# ConectoresEntrada.net
KiCad netlist of a schematic drawn in Altium Designer
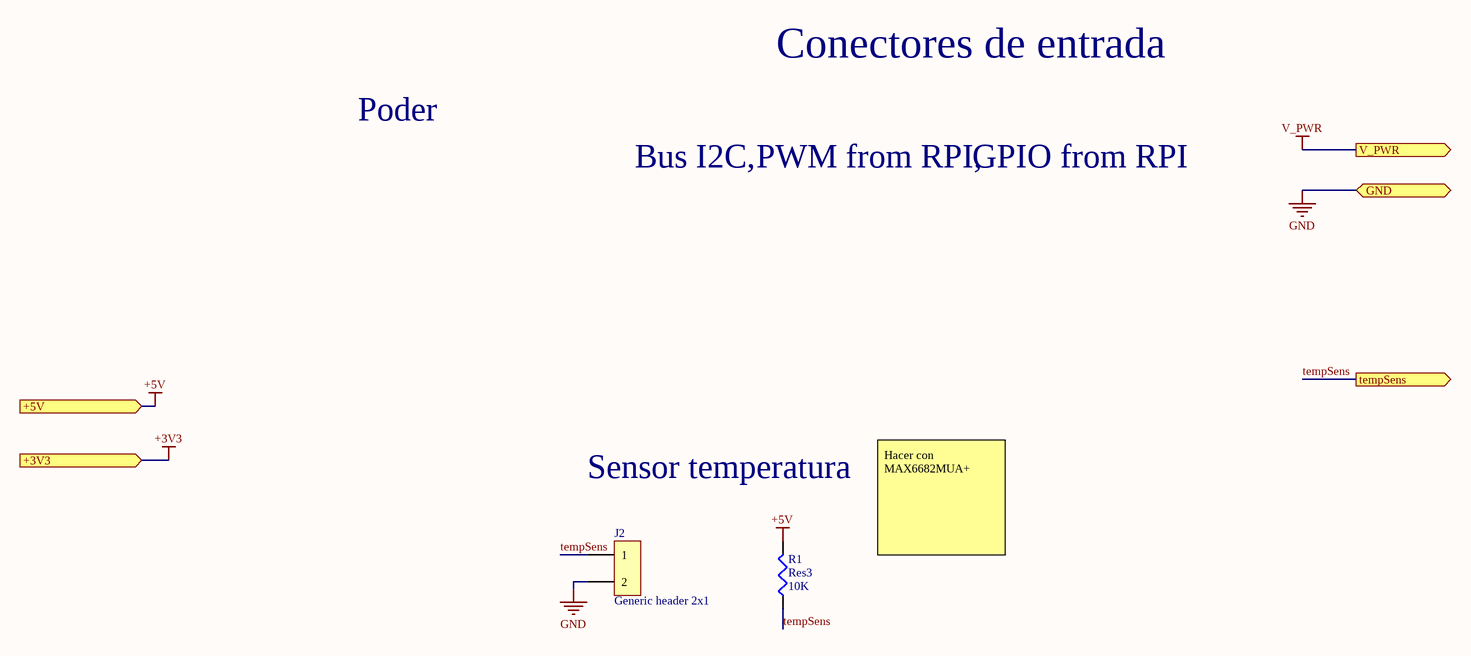
[diagram p0: ConectoresEntrada.SchDoc]

(export (version "E")
  (design (tool "Eeschema 10.0.6"))
  (components
    (comp (ref "J2")
      (value "Generic header 2x1")
      (footprint "CONN-TH_A2547WV-2P")
      (description "Generic Header 2pos, 1 row, 2.54 pitch")
      (fields
        (field (name "MANUFACTURER") "CJT(Changjiang Connectors)")
        (field (name "MANUFACTURER PART NUMBER") "A2547WV-2P")
      )
      (libsource (lib "IoWLabsConnectors") (part "Header - 2x1"))
    )
    (comp (ref "R1")
      (value "Res3")
      (footprint "J1-0603")
      (description "Resistor")
      (fields
        (field (name "ALTIUM_VALUE") "10K")
        (field (name "MANUFACTURER") "PANASONIC")
        (field (name "MANUFACTURER PART NUMBER") "ERJPA3F1002V")
        (field (name "PUBLISHER") "Altium Limited")
      )
      (libsource (lib "Miscellaneous Devices") (part "Res3"))
    )
  )
  (nets
    (net (code "2") (name "+5V") (class "Default")
      (node (ref "R1") (pin "2") (pinfunction "2_2") (pintype "passive"))
    )
    (net (code "3") (name "/tempSens") (class "Default")
      (node (ref "J2") (pin "1") (pinfunction "1_1") (pintype "passive"))
      (node (ref "R1") (pin "1") (pinfunction "1_1") (pintype "passive"))
    )
    (net (code "4") (name "GND") (class "Default")
      (node (ref "J2") (pin "2") (pinfunction "2_2") (pintype "passive"))
    )
  )
)
